# 411RoughDraft.net
KiCad netlist of a schematic drawn in EAGLE
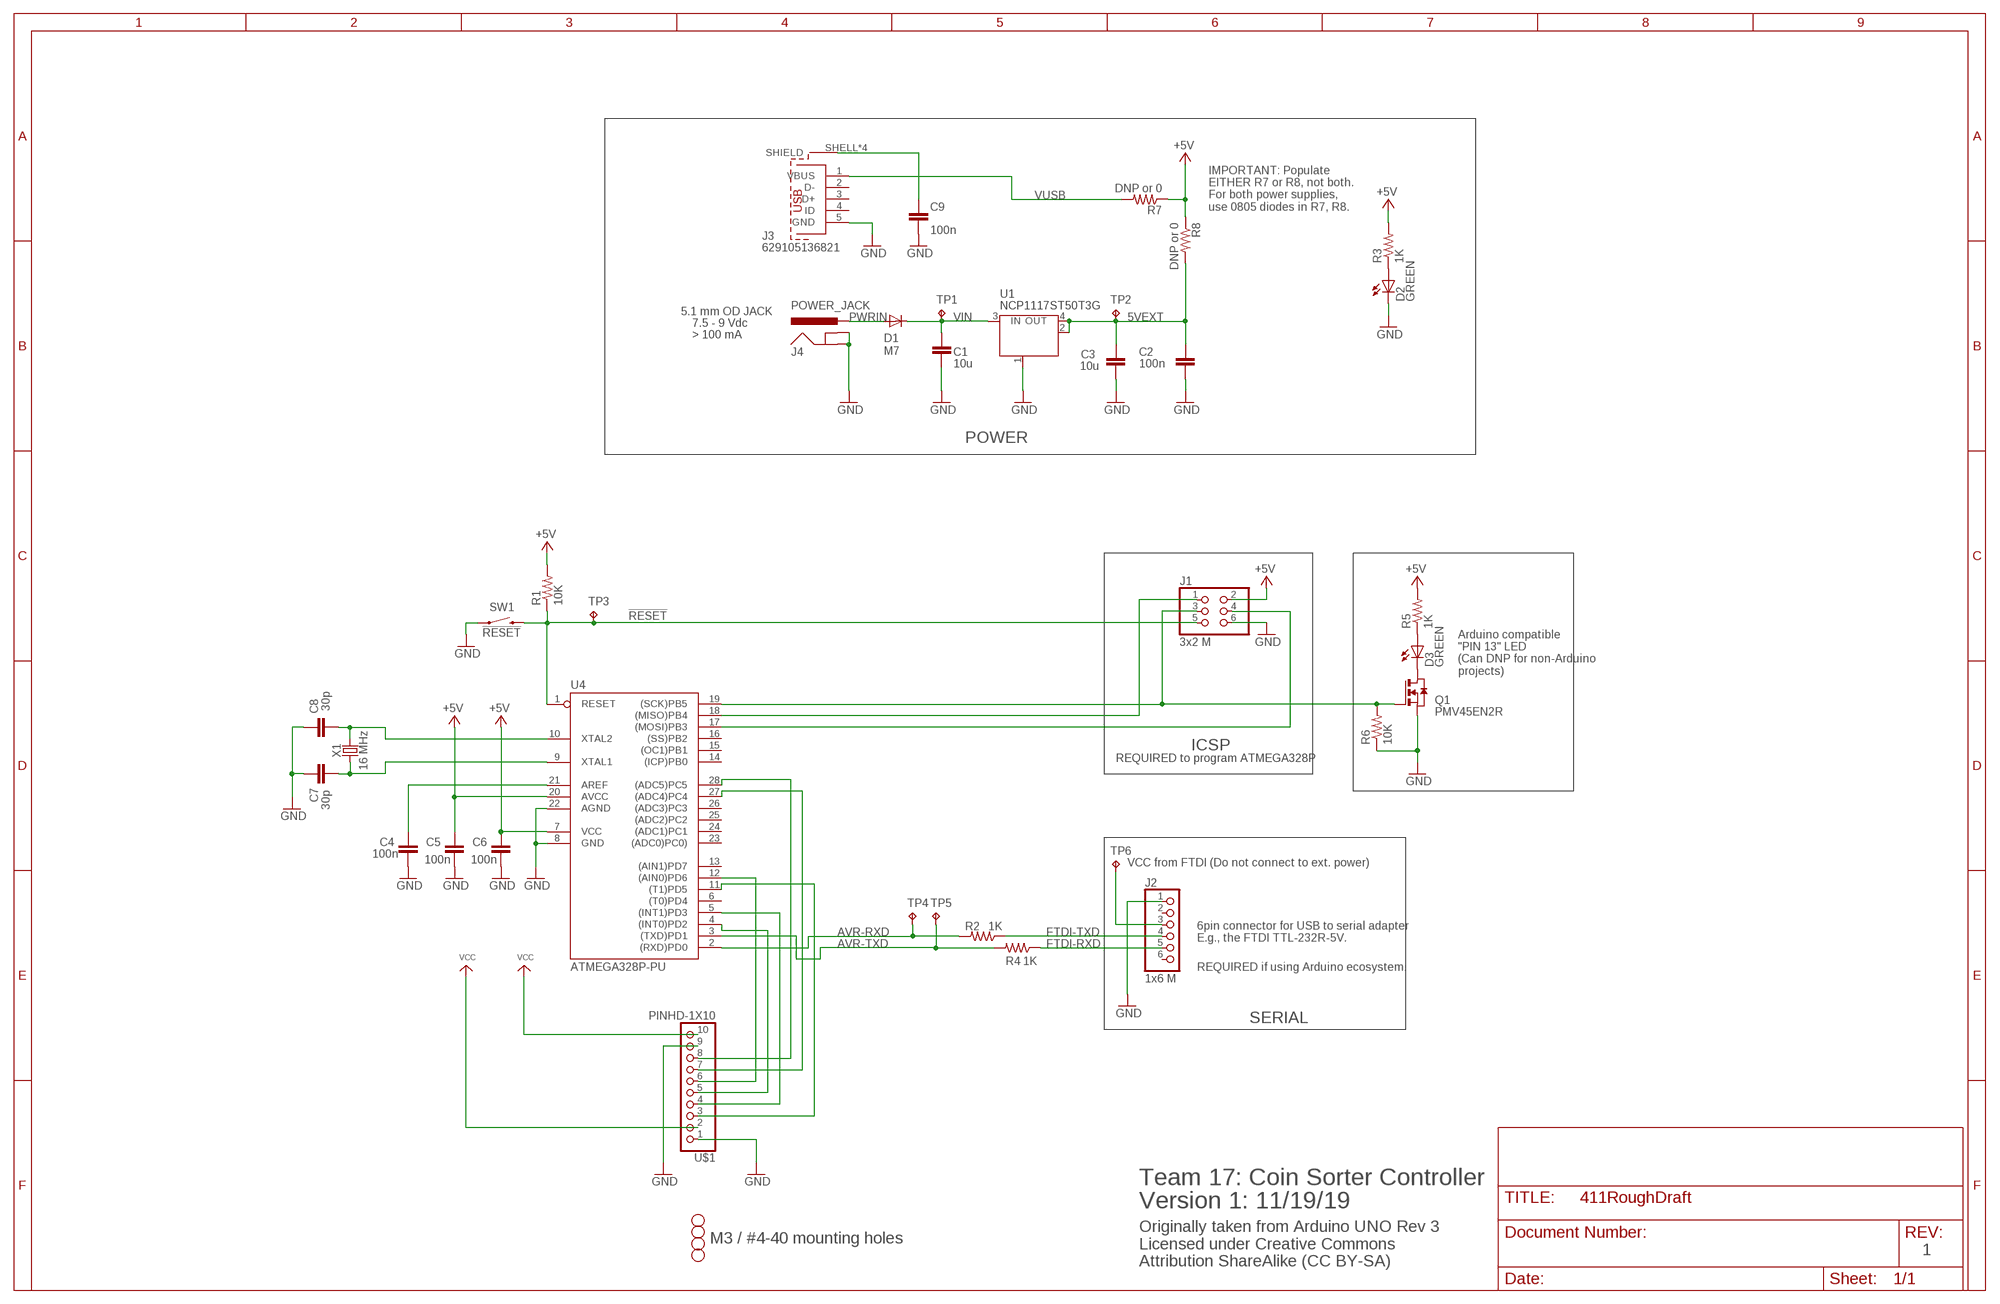
[diagram p0: schematic, sheet 1]

(export (version "E")
  (design (tool "Eeschema 10.0.6"))
  (components
    (comp (ref "C1")
      (value "10u")
      (footprint "eagle-import:C0805K")
      (fields (field (name "MFR") "Samsung") (field (name "MPN") "CL21A106KOQNNNG"))
      (libsource (lib "eagle-import") (part "C-EUC0805K"))
    )
    (comp (ref "C2")
      (value "100n")
      (footprint "eagle-import:C0805K")
      (fields (field (name "MFR") "Samsung") (field (name "MPN") "CL21B104KBCNNNC"))
      (libsource (lib "eagle-import") (part "C-EUC0805K"))
    )
    (comp (ref "C3")
      (value "10u")
      (footprint "eagle-import:C0805K")
      (fields (field (name "MFR") "Samsung") (field (name "MPN") "CL21A106KOQNNNG"))
      (libsource (lib "eagle-import") (part "C-EUC0805K"))
    )
    (comp (ref "C4")
      (value "100n")
      (footprint "eagle-import:C0805K")
      (fields (field (name "MFR") "Samsung") (field (name "MPN") "CL21B104KBCNNNC"))
      (libsource (lib "eagle-import") (part "C-EUC0805K"))
    )
    (comp (ref "C5")
      (value "100n")
      (footprint "eagle-import:C0805K")
      (fields (field (name "MFR") "Samsung") (field (name "MPN") "CL21B104KBCNNNC"))
      (libsource (lib "eagle-import") (part "C-EUC0805K"))
    )
    (comp (ref "C6")
      (value "100n")
      (footprint "eagle-import:C0805K")
      (fields (field (name "MFR") "Samsung") (field (name "MPN") "CL21B104KBCNNNC"))
      (libsource (lib "eagle-import") (part "C-EUC0805K"))
    )
    (comp (ref "C7")
      (value "30p")
      (footprint "eagle-import:C0805K")
      (fields (field (name "MFR") "Samsung") (field (name "MPN") "CL21C180JBANNNC"))
      (libsource (lib "eagle-import") (part "C-EUC0805K"))
    )
    (comp (ref "C8")
      (value "30p")
      (footprint "eagle-import:C0805K")
      (fields (field (name "MFR") "Samsung") (field (name "MPN") "CL21C300JBANNNC"))
      (libsource (lib "eagle-import") (part "C-EUC0805K"))
    )
    (comp (ref "C9")
      (value "100n")
      (footprint "eagle-import:C0805K")
      (fields (field (name "MFR") "Samsung") (field (name "MPN") "CL21B104KBCNNNC"))
      (libsource (lib "eagle-import") (part "C-EUC0805K"))
    )
    (comp (ref "D1")
      (value "M7")
      (footprint "eagle-import:SMB")
      (fields (field (name "MFR") "SMC Diode") (field (name "MPN") "10BQ030TR"))
      (libsource (lib "eagle-import") (part "DIODE-SMB"))
    )
    (comp (ref "D2")
      (value "GREEN")
      (footprint "eagle-import:CHIP-LED0805")
      (fields (field (name "MFR") "Würth Elektronik") (field (name "MPN") "150080GS75000"))
      (libsource (lib "eagle-import") (part "LEDCHIP-LED0805"))
    )
    (comp (ref "D3")
      (value "GREEN")
      (footprint "eagle-import:CHIP-LED0805")
      (fields (field (name "MFR") "Würth Elektronik") (field (name "MPN") "150080GS75000"))
      (libsource (lib "eagle-import") (part "LEDCHIP-LED0805"))
    )
    (comp (ref "H1")
      (value "STAND-OFF")
      (footprint "eagle-import:STAND-OFF")
      (libsource (lib "eagle-import") (part "STAND-OFF"))
    )
    (comp (ref "H2")
      (value "STAND-OFF")
      (footprint "eagle-import:STAND-OFF")
      (libsource (lib "eagle-import") (part "STAND-OFF"))
    )
    (comp (ref "H3")
      (value "STAND-OFF")
      (footprint "eagle-import:STAND-OFF")
      (libsource (lib "eagle-import") (part "STAND-OFF"))
    )
    (comp (ref "H4")
      (value "STAND-OFF")
      (footprint "eagle-import:STAND-OFF")
      (libsource (lib "eagle-import") (part "STAND-OFF"))
    )
    (comp (ref "J1")
      (value "3x2 M")
      (footprint "eagle-import:2X03")
      (fields (field (name "MFR") "Harwin") (field (name "MPN") "M20-9980345"))
      (libsource (lib "eagle-import") (part "PINHD-2X3"))
    )
    (comp (ref "J2")
      (value "1x6 M")
      (footprint "eagle-import:1X06")
      (fields (field (name "MFR") "Sullins") (field (name "MPN") "PRPC006SAAN-RC"))
      (libsource (lib "eagle-import") (part "PINHD-1X6"))
    )
    (comp (ref "J3")
      (value "629105136821")
      (footprint "eagle-import:629105136821")
      (fields (field (name "MFR") "Wurth"))
      (libsource (lib "eagle-import") (part "629105136821"))
    )
    (comp (ref "J4")
      (value "POWER_JACK")
      (footprint "eagle-import:POWER_JACK_PTH")
      (fields (field (name "MFR") "CUI") (field (name "MPN") "PJ-202A"))
      (libsource (lib "eagle-import") (part "POWER_JACK"))
    )
    (comp (ref "Q1")
      (value "PMV45EN2R")
      (footprint "eagle-import:SOT-23")
      (fields (field (name "MFR") "Nexperia") (field (name "MPN") "PMV45EN2R"))
      (libsource (lib "eagle-import") (part "NMOSSOT23"))
    )
    (comp (ref "R1")
      (value "10K")
      (footprint "eagle-import:R0805")
      (fields (field (name "MFR") "Yageo") (field (name "MPN") "RC0805FR-0710KL"))
      (libsource (lib "eagle-import") (part "R-US_R0805"))
    )
    (comp (ref "R2")
      (value "1K")
      (footprint "eagle-import:R0805")
      (fields (field (name "MFR") "Yageo") (field (name "MPN") "RC0805FR-071KL"))
      (libsource (lib "eagle-import") (part "R-US_R0805"))
    )
    (comp (ref "R3")
      (value "1K")
      (footprint "eagle-import:R0805")
      (fields (field (name "MFR") "Yageo") (field (name "MPN") "RC0805FR-071KL"))
      (libsource (lib "eagle-import") (part "R-US_R0805"))
    )
    (comp (ref "R4")
      (value "1K")
      (footprint "eagle-import:R0805")
      (fields (field (name "MFR") "Yageo") (field (name "MPN") "RC0805FR-071KL"))
      (libsource (lib "eagle-import") (part "R-US_R0805"))
    )
    (comp (ref "R5")
      (value "1K")
      (footprint "eagle-import:R0805")
      (fields (field (name "MFR") "Yageo") (field (name "MPN") "RC0805FR-071KL"))
      (libsource (lib "eagle-import") (part "R-US_R0805"))
    )
    (comp (ref "R6")
      (value "10K")
      (footprint "eagle-import:R0805")
      (fields (field (name "MFR") "Yageo") (field (name "MPN") "RC0805FR-0710KL"))
      (libsource (lib "eagle-import") (part "R-US_R0805"))
    )
    (comp (ref "R7")
      (value "DNP or 0")
      (footprint "eagle-import:R0805")
      (fields (field (name "MFR") "Yageo") (field (name "MPN") "RC0805JR-070RL"))
      (libsource (lib "eagle-import") (part "R-US_R0805"))
    )
    (comp (ref "R8")
      (value "DNP or 0")
      (footprint "eagle-import:R0805")
      (fields (field (name "MFR") "Yageo") (field (name "MPN") "RC0805JR-070RL"))
      (libsource (lib "eagle-import") (part "R-US_R0805"))
    )
    (comp (ref "SW1")
      (value "!RESET")
      (footprint "eagle-import:TACTILE_SWITCH_SMD")
      (fields (field (name "MFR") "C&K") (field (name "MPN") "RS-187R05A2-DS MT RT"))
      (libsource (lib "eagle-import") (part "SWITCH-MOMENTARY-2SMD"))
    )
    (comp (ref "TP1")
      (value "TPPAD1-13")
      (footprint "eagle-import:P1-13")
      (libsource (lib "eagle-import") (part "TPPAD1-13"))
    )
    (comp (ref "TP2")
      (value "TPPAD1-13")
      (footprint "eagle-import:P1-13")
      (libsource (lib "eagle-import") (part "TPPAD1-13"))
    )
    (comp (ref "TP3")
      (value "TPPAD1-13")
      (footprint "eagle-import:P1-13")
      (libsource (lib "eagle-import") (part "TPPAD1-13"))
    )
    (comp (ref "TP4")
      (value "TPPAD1-13")
      (footprint "eagle-import:P1-13")
      (libsource (lib "eagle-import") (part "TPPAD1-13"))
    )
    (comp (ref "TP5")
      (value "TPPAD1-13")
      (footprint "eagle-import:P1-13")
      (libsource (lib "eagle-import") (part "TPPAD1-13"))
    )
    (comp (ref "TP6")
      (value "TPPAD1-13")
      (footprint "eagle-import:P1-13")
      (libsource (lib "eagle-import") (part "TPPAD1-13"))
    )
    (comp (ref "U$1")
      (value "PINHD-1X10")
      (footprint "eagle-import:1X10-BIG")
      (libsource (lib "eagle-import") (part "PINHD-1X10"))
    )
    (comp (ref "U1")
      (value "NCP1117ST50T3G")
      (footprint "eagle-import:SOT223")
      (fields (field (name "MFR") "ON Semiconductor"))
      (libsource (lib "eagle-import") (part "MC33269ST-3.3T3"))
    )
    (comp (ref "U4")
      (value "ATMEGA328P-PU")
      (footprint "eagle-import:DIL28-3")
      (fields (field (name "MFR") "Microchip"))
      (libsource (lib "eagle-import") (part "ATMEGA328P-PU"))
    )
    (comp (ref "X1")
      (value "16 MHz")
      (footprint "eagle-import:HC49UP")
      (fields (field (name "MFR") "ECS") (field (name "MPN") "ECS-160-18-5PX-TR"))
      (libsource (lib "eagle-import") (part "CRYSTALSMD-HC49UP"))
    )
  )
  (nets
    (net (code "1") (name "+5V") (class "Default")
      (node (ref "C5") (pin "2") (pinfunction "2_2") (pintype "passive"))
      (node (ref "C6") (pin "2") (pinfunction "2_2") (pintype "passive"))
      (node (ref "J1") (pin "2") (pinfunction "2_2") (pintype "passive"))
      (node (ref "R1") (pin "2") (pinfunction "2_2") (pintype "passive"))
      (node (ref "R3") (pin "2") (pinfunction "2_2") (pintype "passive"))
      (node (ref "R5") (pin "2") (pinfunction "2_2") (pintype "passive"))
      (node (ref "R7") (pin "1") (pinfunction "1_1") (pintype "passive"))
      (node (ref "R8") (pin "1") (pinfunction "1_1") (pintype "passive"))
      (node (ref "U4") (pin "20") (pinfunction "AVCC_20") (pintype "power_in"))
      (node (ref "U4") (pin "7") (pinfunction "VCC_7") (pintype "power_in"))
    )
    (net (code "2") (name "/5VEXT") (class "Default")
      (node (ref "C2") (pin "2") (pinfunction "2_2") (pintype "passive"))
      (node (ref "C3") (pin "1") (pinfunction "1_1") (pintype "passive"))
      (node (ref "R8") (pin "2") (pinfunction "2_2") (pintype "passive"))
      (node (ref "TP2") (pin "TP") (pinfunction "TP_TP") (pintype "input"))
      (node (ref "U1") (pin "2") (pinfunction "OUT_2") (pintype "passive"))
      (node (ref "U1") (pin "4") (pinfunction "OUT_4") (pintype "passive"))
    )
    (net (code "3") (name "/AVR-RXD") (class "Default")
      (node (ref "R2") (pin "2") (pinfunction "2_2") (pintype "passive"))
      (node (ref "TP4") (pin "TP") (pinfunction "TP_TP") (pintype "input"))
      (node (ref "U4") (pin "2") (pinfunction "(RXD)PD0_2") (pintype "bidirectional"))
    )
    (net (code "4") (name "/AVR-TXD") (class "Default")
      (node (ref "R4") (pin "2") (pinfunction "2_2") (pintype "passive"))
      (node (ref "TP5") (pin "TP") (pinfunction "TP_TP") (pintype "input"))
      (node (ref "U4") (pin "3") (pinfunction "(TXD)PD1_3") (pintype "bidirectional"))
    )
    (net (code "5") (name "/FTDI-RXD") (class "Default")
      (node (ref "J2") (pin "5") (pinfunction "5_5") (pintype "passive"))
      (node (ref "R4") (pin "1") (pinfunction "1_1") (pintype "passive"))
    )
    (net (code "6") (name "/FTDI-TXD") (class "Default")
      (node (ref "J2") (pin "4") (pinfunction "4_4") (pintype "passive"))
      (node (ref "R2") (pin "1") (pinfunction "1_1") (pintype "passive"))
    )
    (net (code "7") (name "/PWRIN") (class "Default")
      (node (ref "D1") (pin "A") (pinfunction "A_A") (pintype "passive"))
      (node (ref "J4") (pin "PWR") (pinfunction "PWR_PWR") (pintype "bidirectional"))
    )
    (net (code "8") (name "/VIN") (class "Default")
      (node (ref "C1") (pin "1") (pinfunction "1_1") (pintype "passive"))
      (node (ref "D1") (pin "C") (pinfunction "C_C") (pintype "passive"))
      (node (ref "TP1") (pin "TP") (pinfunction "TP_TP") (pintype "input"))
      (node (ref "U1") (pin "3") (pinfunction "IN_3") (pintype "input"))
    )
    (net (code "9") (name "/VUSB") (class "Default")
      (node (ref "J3") (pin "1") (pinfunction "VBUS_1") (pintype "passive"))
      (node (ref "R7") (pin "2") (pinfunction "2_2") (pintype "passive"))
    )
    (net (code "10") (name "/~{RESET}") (class "Default")
      (node (ref "J1") (pin "5") (pinfunction "5_5") (pintype "passive"))
      (node (ref "R1") (pin "1") (pinfunction "1_1") (pintype "passive"))
      (node (ref "SW1") (pin "3") (pinfunction "2_3") (pintype "passive"))
      (node (ref "TP3") (pin "TP") (pinfunction "TP_TP") (pintype "input"))
      (node (ref "U4") (pin "1") (pinfunction "RESET_1") (pintype "input"))
    )
    (net (code "11") (name "GND") (class "Default")
      (node (ref "C1") (pin "2") (pinfunction "2_2") (pintype "passive"))
      (node (ref "C2") (pin "1") (pinfunction "1_1") (pintype "passive"))
      (node (ref "C3") (pin "2") (pinfunction "2_2") (pintype "passive"))
      (node (ref "C4") (pin "1") (pinfunction "1_1") (pintype "passive"))
      (node (ref "C5") (pin "1") (pinfunction "1_1") (pintype "passive"))
      (node (ref "C6") (pin "1") (pinfunction "1_1") (pintype "passive"))
      (node (ref "C7") (pin "2") (pinfunction "2_2") (pintype "passive"))
      (node (ref "C8") (pin "2") (pinfunction "2_2") (pintype "passive"))
      (node (ref "C9") (pin "1") (pinfunction "1_1") (pintype "passive"))
      (node (ref "D2") (pin "C") (pinfunction "C_C") (pintype "passive"))
      (node (ref "J1") (pin "6") (pinfunction "6_6") (pintype "passive"))
      (node (ref "J2") (pin "1") (pinfunction "1_1") (pintype "passive"))
      (node (ref "J3") (pin "5") (pinfunction "GND_5") (pintype "passive"))
      (node (ref "J4") (pin "GND") (pinfunction "GND_GND") (pintype "bidirectional"))
      (node (ref "J4") (pin "GNDBREAK") (pinfunction "GNDBREAK_GNDBREAK") (pintype "bidirectional"))
      (node (ref "Q1") (pin "2") (pinfunction "S_2") (pintype "passive"))
      (node (ref "R6") (pin "1") (pinfunction "1_1") (pintype "passive"))
      (node (ref "SW1") (pin "1") (pinfunction "1_1") (pintype "passive"))
      (node (ref "U$1") (pin "1") (pinfunction "1_1") (pintype "passive"))
      (node (ref "U$1") (pin "9") (pinfunction "9_9") (pintype "passive"))
      (node (ref "U1") (pin "1") (pinfunction "GND/ADJ_1") (pintype "input"))
      (node (ref "U4") (pin "22") (pinfunction "AGND_22") (pintype "power_in"))
      (node (ref "U4") (pin "8") (pinfunction "GND_8") (pintype "power_in"))
    )
    (net (code "12") (name "Net-(C9-Pad2)") (class "Default")
      (node (ref "C9") (pin "2") (pinfunction "2_2") (pintype "passive"))
      (node (ref "J3") (pin "SHELL") (pinfunction "SHIELD_SHELL") (pintype "passive"))
      (node (ref "J3") (pin "SHELL1") (pinfunction "SHIELD_SHELL1") (pintype "passive"))
      (node (ref "J3") (pin "SHELL2") (pinfunction "SHIELD_SHELL2") (pintype "passive"))
      (node (ref "J3") (pin "SHELL3") (pinfunction "SHIELD_SHELL3") (pintype "passive"))
    )
    (net (code "13") (name "Net-(D2-PadA)") (class "Default")
      (node (ref "D2") (pin "A") (pinfunction "A_A") (pintype "passive"))
      (node (ref "R3") (pin "1") (pinfunction "1_1") (pintype "passive"))
    )
    (net (code "14") (name "Net-(D3-PadA)") (class "Default")
      (node (ref "D3") (pin "A") (pinfunction "A_A") (pintype "passive"))
      (node (ref "R5") (pin "1") (pinfunction "1_1") (pintype "passive"))
    )
    (net (code "15") (name "Net-(J2-Pad3)") (class "Default")
      (node (ref "J2") (pin "3") (pinfunction "3_3") (pintype "passive"))
      (node (ref "TP6") (pin "TP") (pinfunction "TP_TP") (pintype "input"))
    )
    (net (code "16") (name "Net-(Q1-D)") (class "Default")
      (node (ref "D3") (pin "C") (pinfunction "C_C") (pintype "passive"))
      (node (ref "Q1") (pin "1") (pinfunction "D_1") (pintype "passive"))
    )
    (net (code "17") (name "Net-(Q1-G)") (class "Default")
      (node (ref "J1") (pin "3") (pinfunction "3_3") (pintype "passive"))
      (node (ref "Q1") (pin "3") (pinfunction "G_3") (pintype "passive"))
      (node (ref "R6") (pin "2") (pinfunction "2_2") (pintype "passive"))
      (node (ref "U4") (pin "19") (pinfunction "(SCK)PB5_19") (pintype "bidirectional"))
    )
    (net (code "18") (name "Net-(U4-(ADC4)PC4)") (class "Default")
      (node (ref "U$1") (pin "7") (pinfunction "7_7") (pintype "passive"))
      (node (ref "U4") (pin "27") (pinfunction "(ADC4)PC4_27") (pintype "bidirectional"))
    )
    (net (code "19") (name "Net-(U4-(ADC5)PC5)") (class "Default")
      (node (ref "U$1") (pin "8") (pinfunction "8_8") (pintype "passive"))
      (node (ref "U4") (pin "28") (pinfunction "(ADC5)PC5_28") (pintype "bidirectional"))
    )
    (net (code "20") (name "Net-(U4-(AIN0)PD6)") (class "Default")
      (node (ref "U$1") (pin "6") (pinfunction "6_6") (pintype "passive"))
      (node (ref "U4") (pin "12") (pinfunction "(AIN0)PD6_12") (pintype "bidirectional"))
    )
    (net (code "21") (name "Net-(U4-(INT0)PD2)") (class "Default")
      (node (ref "U$1") (pin "5") (pinfunction "5_5") (pintype "passive"))
      (node (ref "U4") (pin "4") (pinfunction "(INT0)PD2_4") (pintype "bidirectional"))
    )
    (net (code "22") (name "Net-(U4-(INT1)PD3)") (class "Default")
      (node (ref "U$1") (pin "4") (pinfunction "4_4") (pintype "passive"))
      (node (ref "U4") (pin "5") (pinfunction "(INT1)PD3_5") (pintype "bidirectional"))
    )
    (net (code "23") (name "Net-(U4-(MISO)PB4)") (class "Default")
      (node (ref "J1") (pin "1") (pinfunction "1_1") (pintype "passive"))
      (node (ref "U4") (pin "18") (pinfunction "(MISO)PB4_18") (pintype "bidirectional"))
    )
    (net (code "24") (name "Net-(U4-(MOSI)PB3)") (class "Default")
      (node (ref "J1") (pin "4") (pinfunction "4_4") (pintype "passive"))
      (node (ref "U4") (pin "17") (pinfunction "(MOSI)PB3_17") (pintype "bidirectional"))
    )
    (net (code "25") (name "Net-(U4-(T1)PD5)") (class "Default")
      (node (ref "U$1") (pin "3") (pinfunction "3_3") (pintype "passive"))
      (node (ref "U4") (pin "11") (pinfunction "(T1)PD5_11") (pintype "bidirectional"))
    )
    (net (code "26") (name "Net-(U4-AREF)") (class "Default")
      (node (ref "C4") (pin "2") (pinfunction "2_2") (pintype "passive"))
      (node (ref "U4") (pin "21") (pinfunction "AREF_21") (pintype "passive"))
    )
    (net (code "27") (name "Net-(U4-XTAL1)") (class "Default")
      (node (ref "C7") (pin "1") (pinfunction "1_1") (pintype "passive"))
      (node (ref "U4") (pin "9") (pinfunction "XTAL1_9") (pintype "bidirectional"))
      (node (ref "X1") (pin "1") (pinfunction "1_1") (pintype "passive"))
    )
    (net (code "28") (name "Net-(U4-XTAL2)") (class "Default")
      (node (ref "C8") (pin "1") (pinfunction "1_1") (pintype "passive"))
      (node (ref "U4") (pin "10") (pinfunction "XTAL2_10") (pintype "bidirectional"))
      (node (ref "X1") (pin "2") (pinfunction "2_2") (pintype "passive"))
    )
    (net (code "29") (name "VCC") (class "Default")
      (node (ref "U$1") (pin "10") (pinfunction "10_10") (pintype "passive"))
      (node (ref "U$1") (pin "2") (pinfunction "2_2") (pintype "passive"))
    )
    (net (code "30") (name "unconnected-(J2-Pad2)") (class "Default")
      (node (ref "J2") (pin "2") (pinfunction "2_2") (pintype "passive"))
    )
    (net (code "31") (name "unconnected-(J2-Pad6)") (class "Default")
      (node (ref "J2") (pin "6") (pinfunction "6_6") (pintype "passive"))
    )
    (net (code "32") (name "unconnected-(J3-D+-Pad3)") (class "Default")
      (node (ref "J3") (pin "3") (pinfunction "D+_3") (pintype "passive"))
    )
    (net (code "33") (name "unconnected-(J3-D--Pad2)") (class "Default")
      (node (ref "J3") (pin "2") (pinfunction "D-_2") (pintype "passive"))
    )
    (net (code "34") (name "unconnected-(J3-ID-Pad4)") (class "Default")
      (node (ref "J3") (pin "4") (pinfunction "ID_4") (pintype "passive"))
    )
    (net (code "35") (name "unconnected-(U4-(ADC0)PC0)-Pad23)") (class "Default")
      (node (ref "U4") (pin "23") (pinfunction "(ADC0)PC0)_23") (pintype "bidirectional"))
    )
    (net (code "36") (name "unconnected-(U4-(ADC1)PC1-Pad24)") (class "Default")
      (node (ref "U4") (pin "24") (pinfunction "(ADC1)PC1_24") (pintype "bidirectional"))
    )
    (net (code "37") (name "unconnected-(U4-(ADC2)PC2-Pad25)") (class "Default")
      (node (ref "U4") (pin "25") (pinfunction "(ADC2)PC2_25") (pintype "bidirectional"))
    )
    (net (code "38") (name "unconnected-(U4-(ADC3)PC3-Pad26)") (class "Default")
      (node (ref "U4") (pin "26") (pinfunction "(ADC3)PC3_26") (pintype "bidirectional"))
    )
    (net (code "39") (name "unconnected-(U4-(AIN1)PD7-Pad13)") (class "Default")
      (node (ref "U4") (pin "13") (pinfunction "(AIN1)PD7_13") (pintype "bidirectional"))
    )
    (net (code "40") (name "unconnected-(U4-(ICP)PB0-Pad14)") (class "Default")
      (node (ref "U4") (pin "14") (pinfunction "(ICP)PB0_14") (pintype "bidirectional"))
    )
    (net (code "41") (name "unconnected-(U4-(OC1)PB1-Pad15)") (class "Default")
      (node (ref "U4") (pin "15") (pinfunction "(OC1)PB1_15") (pintype "bidirectional"))
    )
    (net (code "42") (name "unconnected-(U4-(SS)PB2-Pad16)") (class "Default")
      (node (ref "U4") (pin "16") (pinfunction "(SS)PB2_16") (pintype "bidirectional"))
    )
    (net (code "43") (name "unconnected-(U4-(T0)PD4-Pad6)") (class "Default")
      (node (ref "U4") (pin "6") (pinfunction "(T0)PD4_6") (pintype "bidirectional"))
    )
  )
)
